# IBUS_adapter.net
KiCad netlist of a schematic drawn in EAGLE
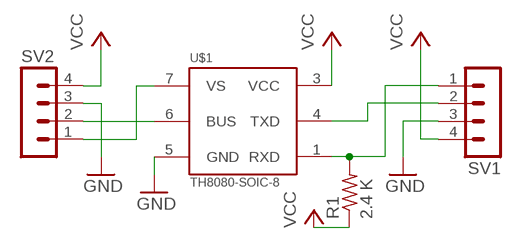
[diagram p0: schematic, sheet 1]

(export (version "E")
  (design (tool "Eeschema 10.0.6"))
  (components
    (comp (ref "R1")
      (value "2.4 K")
      (footprint "eagle-import:R1206")
      (libsource (lib "eagle-import") (part "R-US_R1206"))
    )
    (comp (ref "SV1")
      (value "MA04-1")
      (footprint "eagle-import:MA04-1")
      (libsource (lib "eagle-import") (part "MA04-1"))
    )
    (comp (ref "SV2")
      (value "MA04-1")
      (footprint "eagle-import:MA04-1")
      (libsource (lib "eagle-import") (part "MA04-1"))
    )
    (comp (ref "U$1")
      (value "TH8080-SOIC-8")
      (footprint "eagle-import:SO-8")
      (libsource (lib "eagle-import") (part "TH8080-SOIC-8"))
    )
  )
  (nets
    (net (code "1") (name "GND") (class "Default")
      (node (ref "SV1") (pin "3") (pinfunction "3_3") (pintype "passive"))
      (node (ref "SV2") (pin "3") (pinfunction "3_3") (pintype "passive"))
      (node (ref "U$1") (pin "5") (pinfunction "GND_5") (pintype "power_in"))
    )
    (net (code "2") (name "Net-(U$1-BUS)") (class "Default")
      (node (ref "SV2") (pin "2") (pinfunction "2_2") (pintype "passive"))
      (node (ref "U$1") (pin "6") (pinfunction "BUS_6") (pintype "bidirectional"))
    )
    (net (code "3") (name "Net-(U$1-RXD)") (class "Default")
      (node (ref "R1") (pin "2") (pinfunction "2_2") (pintype "passive"))
      (node (ref "SV1") (pin "1") (pinfunction "1_1") (pintype "passive"))
      (node (ref "U$1") (pin "1") (pinfunction "RXD_1") (pintype "output"))
    )
    (net (code "4") (name "Net-(U$1-TXD)") (class "Default")
      (node (ref "SV1") (pin "2") (pinfunction "2_2") (pintype "passive"))
      (node (ref "U$1") (pin "4") (pinfunction "TXD_4") (pintype "input"))
    )
    (net (code "5") (name "Net-(U$1-VS)") (class "Default")
      (node (ref "SV2") (pin "1") (pinfunction "1_1") (pintype "passive"))
      (node (ref "U$1") (pin "7") (pinfunction "VS_7") (pintype "power_in"))
    )
    (net (code "6") (name "VCC") (class "Default")
      (node (ref "R1") (pin "1") (pinfunction "1_1") (pintype "passive"))
      (node (ref "SV1") (pin "4") (pinfunction "4_4") (pintype "passive"))
      (node (ref "SV2") (pin "4") (pinfunction "4_4") (pintype "passive"))
      (node (ref "U$1") (pin "3") (pinfunction "VCC_3") (pintype "power_in"))
    )
  )
)
